# main.net
KiCad netlist of a schematic drawn in Altium Designer
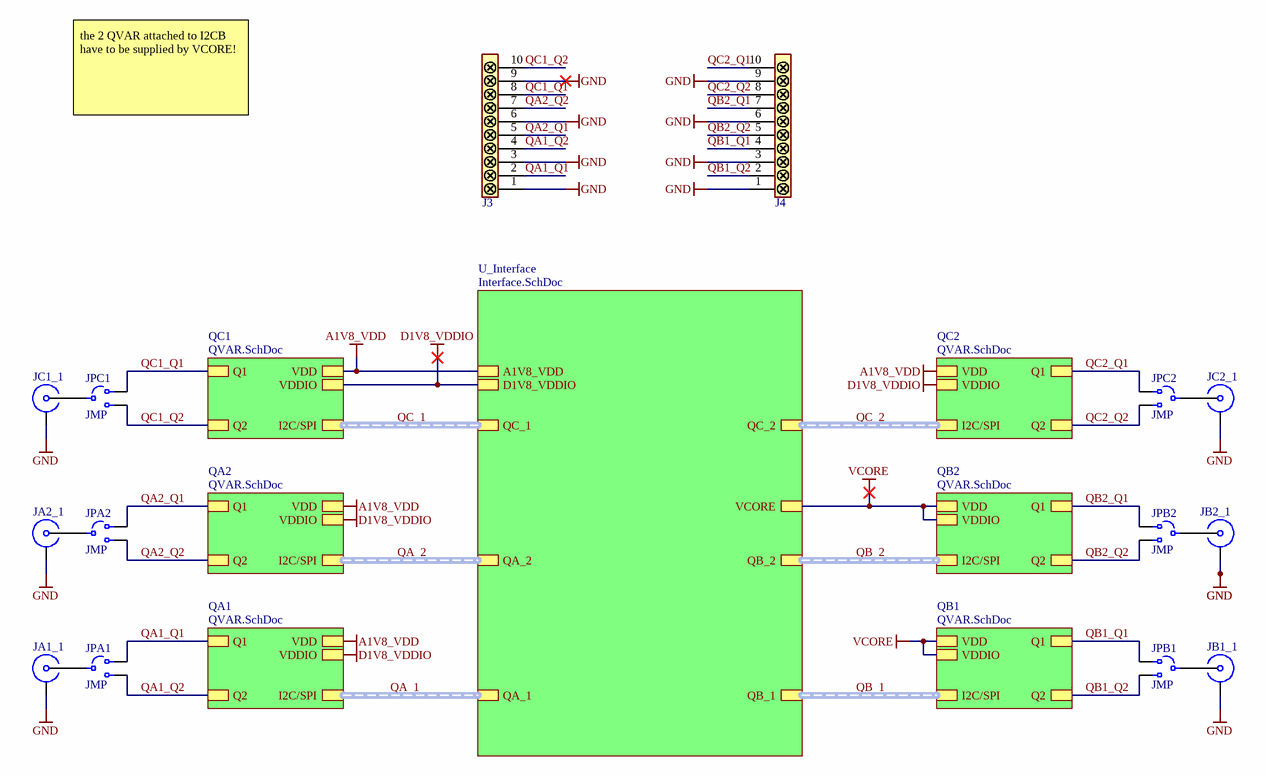
[diagram p0: main.SchDoc]

(export (version "E")
  (design (tool "Eeschema 10.0.6"))
  (components
    (comp (ref "J3")
      (value "FTS-110-01-L-S")
      (footprint "SAMTEC-FTS-110-01-L-S")
      (description "Pinheader 10 pin, 1.27mm")
      (fields (field (name "MANUFACTURER") "Samtec"))
      (libsource (lib "") (part "FTS-110-01-L-S_1"))
    )
    (comp (ref "J4")
      (value "FTS-110-01-L-S")
      (footprint "SAMTEC-FTS-110-01-L-S")
      (description "Pinheader 10 pin, 1.27mm")
      (fields (field (name "MANUFACTURER") "Samtec"))
      (libsource (lib "6QChan_vitalcore_backpack") (part "FTS-110-01-L-S"))
    )
    (comp (ref "JA1_1")
      (value "CONMHF1-SMD-G-T")
      (footprint "C-CONMHF1-SMD-G-T")
      (description "Conn Umc Jack Str SMD")
      (fields (field (name "MANUFACTURER") "TE Connectivity"))
      (libsource (lib "6QChan_vitalcore_backpack") (part "CONMHF1-SMD-G-T"))
    )
    (comp (ref "JA2_1")
      (value "CONMHF1-SMD-G-T")
      (footprint "C-CONMHF1-SMD-G-T")
      (description "Conn Umc Jack Str SMD")
      (fields (field (name "MANUFACTURER") "TE Connectivity"))
      (libsource (lib "6QChan_vitalcore_backpack") (part "CONMHF1-SMD-G-T"))
    )
    (comp (ref "JB1_1")
      (value "CONMHF1-SMD-G-T")
      (footprint "C-CONMHF1-SMD-G-T")
      (description "Conn Umc Jack Str SMD")
      (fields (field (name "MANUFACTURER") "TE Connectivity"))
      (libsource (lib "") (part "CONMHF1-SMD-G-T_1"))
    )
    (comp (ref "JB2_1")
      (value "CONMHF1-SMD-G-T")
      (footprint "C-CONMHF1-SMD-G-T")
      (description "Conn Umc Jack Str SMD")
      (fields (field (name "MANUFACTURER") "TE Connectivity"))
      (libsource (lib "") (part "CONMHF1-SMD-G-T_1"))
    )
    (comp (ref "JC1_1")
      (value "CONMHF1-SMD-G-T")
      (footprint "C-CONMHF1-SMD-G-T")
      (description "Conn Umc Jack Str SMD")
      (fields (field (name "MANUFACTURER") "TE Connectivity"))
      (libsource (lib "6QChan_vitalcore_backpack") (part "CONMHF1-SMD-G-T"))
    )
    (comp (ref "JC2_1")
      (value "CONMHF1-SMD-G-T")
      (footprint "C-CONMHF1-SMD-G-T")
      (description "Conn Umc Jack Str SMD")
      (fields (field (name "MANUFACTURER") "TE Connectivity"))
      (libsource (lib "") (part "CONMHF1-SMD-G-T_1"))
    )
    (comp (ref "JPA1")
      (value "JMP")
      (footprint "JMP_0201_3way")
      (description "JMP 0201 3W")
      (fields
        (field (name "MANUFACTURER") "Panasonic")
        (field (name "MANUFACTURER PART NUMBER") "ERJ-1GN0R00C")
      )
      (libsource (lib "") (part "JMP_0201_3w_1"))
    )
    (comp (ref "JPA2")
      (value "JMP")
      (footprint "JMP_0201_3way")
      (description "JMP 0201 3W")
      (fields
        (field (name "MANUFACTURER") "Panasonic")
        (field (name "MANUFACTURER PART NUMBER") "ERJ-1GN0R00C")
      )
      (libsource (lib "") (part "JMP_0201_3w_1"))
    )
    (comp (ref "JPB1")
      (value "JMP")
      (footprint "JMP_0201_3way")
      (description "JMP 0201 3W")
      (fields
        (field (name "MANUFACTURER") "Panasonic")
        (field (name "MANUFACTURER PART NUMBER") "ERJ-1GN0R00C")
      )
      (libsource (lib "6QChan_vitalcore_backpack") (part "JMP_0201_3w"))
    )
    (comp (ref "JPB2")
      (value "JMP")
      (footprint "JMP_0201_3way")
      (description "JMP 0201 3W")
      (fields
        (field (name "MANUFACTURER") "Panasonic")
        (field (name "MANUFACTURER PART NUMBER") "ERJ-1GN0R00C")
      )
      (libsource (lib "6QChan_vitalcore_backpack") (part "JMP_0201_3w"))
    )
    (comp (ref "JPC1")
      (value "JMP")
      (footprint "JMP_0201_3way")
      (description "JMP 0201 3W")
      (fields
        (field (name "MANUFACTURER") "Panasonic")
        (field (name "MANUFACTURER PART NUMBER") "ERJ-1GN0R00C")
      )
      (libsource (lib "") (part "JMP_0201_3w_1"))
    )
    (comp (ref "JPC2")
      (value "JMP")
      (footprint "JMP_0201_3way")
      (description "JMP 0201 3W")
      (fields
        (field (name "MANUFACTURER") "Panasonic")
        (field (name "MANUFACTURER PART NUMBER") "ERJ-1GN0R00C")
      )
      (libsource (lib "6QChan_vitalcore_backpack") (part "JMP_0201_3w"))
    )
  )
  (nets
    (net (code "7") (name "/QA1_Q1") (class "Default")
      (node (ref "J3") (pin "2") (pintype "passive"))
      (node (ref "JPA1") (pin "1") (pinfunction "1_1") (pintype "passive"))
    )
    (net (code "8") (name "/QA1_Q2") (class "Default")
      (node (ref "J3") (pin "4") (pintype "passive"))
      (node (ref "JPA1") (pin "3") (pinfunction "3_3") (pintype "passive"))
    )
    (net (code "9") (name "/QA2_Q1") (class "Default")
      (node (ref "J3") (pin "5") (pintype "passive"))
      (node (ref "JPA2") (pin "1") (pinfunction "1_1") (pintype "passive"))
    )
    (net (code "10") (name "/QA2_Q2") (class "Default")
      (node (ref "J3") (pin "7") (pintype "passive"))
      (node (ref "JPA2") (pin "3") (pinfunction "3_3") (pintype "passive"))
    )
    (net (code "11") (name "/QB1_Q1") (class "Default")
      (node (ref "J4") (pin "4") (pintype "passive"))
      (node (ref "JPB1") (pin "1") (pinfunction "1_1") (pintype "passive"))
    )
    (net (code "12") (name "/QB1_Q2") (class "Default")
      (node (ref "J4") (pin "2") (pintype "passive"))
      (node (ref "JPB1") (pin "3") (pinfunction "3_3") (pintype "passive"))
    )
    (net (code "13") (name "/QB2_Q1") (class "Default")
      (node (ref "J4") (pin "7") (pintype "passive"))
      (node (ref "JPB2") (pin "1") (pinfunction "1_1") (pintype "passive"))
    )
    (net (code "14") (name "/QB2_Q2") (class "Default")
      (node (ref "J4") (pin "5") (pintype "passive"))
      (node (ref "JPB2") (pin "3") (pinfunction "3_3") (pintype "passive"))
    )
    (net (code "15") (name "/QC1_Q1") (class "Default")
      (node (ref "J3") (pin "8") (pintype "passive"))
      (node (ref "JPC1") (pin "1") (pinfunction "1_1") (pintype "passive"))
    )
    (net (code "16") (name "/QC1_Q2") (class "Default")
      (node (ref "J3") (pin "10") (pintype "passive"))
      (node (ref "JPC1") (pin "3") (pinfunction "3_3") (pintype "passive"))
    )
    (net (code "17") (name "/QC2_Q1") (class "Default")
      (node (ref "J4") (pin "10") (pintype "passive"))
      (node (ref "JPC2") (pin "1") (pinfunction "1_1") (pintype "passive"))
    )
    (net (code "18") (name "/QC2_Q2") (class "Default")
      (node (ref "J4") (pin "8") (pintype "passive"))
      (node (ref "JPC2") (pin "3") (pinfunction "3_3") (pintype "passive"))
    )
    (net (code "27") (name "GND") (class "Default")
      (node (ref "J3") (pin "1") (pintype "passive"))
      (node (ref "J3") (pin "3") (pintype "passive"))
      (node (ref "J3") (pin "6") (pintype "passive"))
      (node (ref "J3") (pin "9") (pintype "passive"))
      (node (ref "J4") (pin "1") (pintype "passive"))
      (node (ref "J4") (pin "3") (pintype "passive"))
      (node (ref "J4") (pin "6") (pintype "passive"))
      (node (ref "J4") (pin "9") (pintype "passive"))
      (node (ref "JA1_1") (pin "G") (pinfunction "G_G") (pintype "passive"))
      (node (ref "JA2_1") (pin "G") (pinfunction "G_G") (pintype "passive"))
      (node (ref "JB1_1") (pin "G") (pinfunction "G_G") (pintype "passive"))
      (node (ref "JB2_1") (pin "G") (pinfunction "G_G") (pintype "passive"))
      (node (ref "JC1_1") (pin "G") (pinfunction "G_G") (pintype "passive"))
      (node (ref "JC2_1") (pin "G") (pinfunction "G_G") (pintype "passive"))
    )
    (net (code "28") (name "Net-(JA1_1-PadS)") (class "Default")
      (node (ref "JA1_1") (pin "S") (pinfunction "S_S") (pintype "passive"))
      (node (ref "JPA1") (pin "2") (pinfunction "2_2") (pintype "passive"))
    )
    (net (code "29") (name "Net-(JA2_1-PadS)") (class "Default")
      (node (ref "JA2_1") (pin "S") (pinfunction "S_S") (pintype "passive"))
      (node (ref "JPA2") (pin "2") (pinfunction "2_2") (pintype "passive"))
    )
    (net (code "30") (name "Net-(JB1_1-PadS)") (class "Default")
      (node (ref "JB1_1") (pin "S") (pinfunction "S_S") (pintype "passive"))
      (node (ref "JPB1") (pin "2") (pinfunction "2_2") (pintype "passive"))
    )
    (net (code "31") (name "Net-(JB2_1-PadS)") (class "Default")
      (node (ref "JB2_1") (pin "S") (pinfunction "S_S") (pintype "passive"))
      (node (ref "JPB2") (pin "2") (pinfunction "2_2") (pintype "passive"))
    )
    (net (code "32") (name "Net-(JC1_1-PadS)") (class "Default")
      (node (ref "JC1_1") (pin "S") (pinfunction "S_S") (pintype "passive"))
      (node (ref "JPC1") (pin "2") (pinfunction "2_2") (pintype "passive"))
    )
    (net (code "33") (name "Net-(JC2_1-PadS)") (class "Default")
      (node (ref "JC2_1") (pin "S") (pinfunction "S_S") (pintype "passive"))
      (node (ref "JPC2") (pin "2") (pinfunction "2_2") (pintype "passive"))
    )
  )
)
